# mixer.net
KiCad netlist of a schematic drawn in Altium Designer
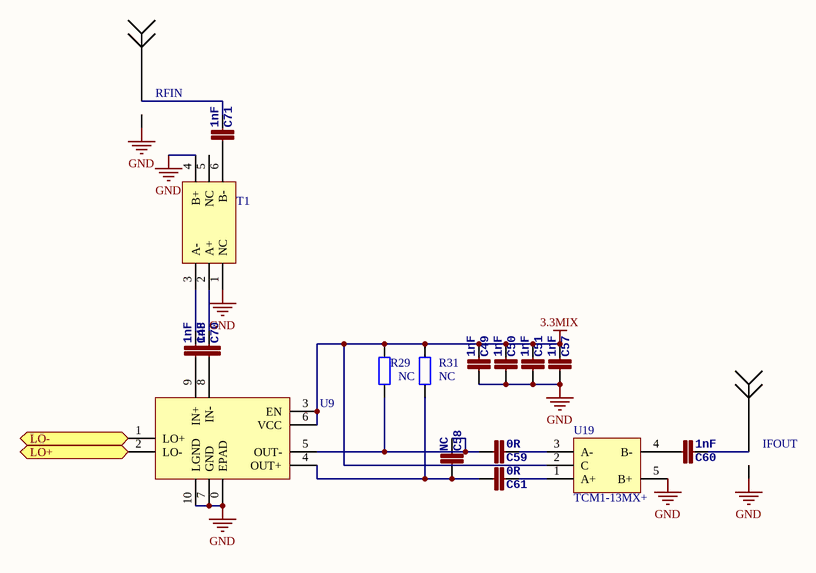
[diagram p0: mixer.SchDoc]

(export (version "E")
  (design (tool "Eeschema 10.0.6"))
  (components
    (comp (ref "C48")
      (value "1nF")
      (footprint "0402")
      (description "<b>Capacitor</b>\nStandard 0603 ceramic capacitor, and 0.1\" leaded capacitor.")
      (fields (field (name "PARTNO") "CC0402ZRY5V7BB104"))
      (libsource (lib "*") (part "CAP0402-CAP"))
    )
    (comp (ref "C49")
      (value "1nF")
      (footprint "0402")
      (description "<b>Capacitor</b>\nStandard 0603 ceramic capacitor, and 0.1\" leaded capacitor.")
      (fields (field (name "PARTNO") "CC0402ZRY5V7BB104"))
      (libsource (lib "*") (part "CAP0402-CAP"))
    )
    (comp (ref "C50")
      (value "1nF")
      (footprint "0402")
      (description "<b>Capacitor</b>\nStandard 0603 ceramic capacitor, and 0.1\" leaded capacitor.")
      (fields (field (name "PARTNO") "CC0402ZRY5V7BB104"))
      (libsource (lib "*") (part "CAP0402-CAP"))
    )
    (comp (ref "C51")
      (value "1nF")
      (footprint "0402")
      (description "<b>Capacitor</b>\nStandard 0603 ceramic capacitor, and 0.1\" leaded capacitor.")
      (fields (field (name "PARTNO") "CC0402ZRY5V7BB104"))
      (libsource (lib "*") (part "CAP0402-CAP"))
    )
    (comp (ref "C57")
      (value "1nF")
      (footprint "0402")
      (description "<b>Capacitor</b>\nStandard 0603 ceramic capacitor, and 0.1\" leaded capacitor.")
      (fields (field (name "PARTNO") "CC0402ZRY5V7BB104"))
      (libsource (lib "*") (part "CAP0402-CAP"))
    )
    (comp (ref "C58")
      (value "NC")
      (footprint "0402")
      (description "<b>Capacitor</b>\nStandard 0603 ceramic capacitor, and 0.1\" leaded capacitor.")
      (fields (field (name "PARTNO") "CC0402ZRY5V7BB104"))
      (libsource (lib "*") (part "CAP0402-CAP"))
    )
    (comp (ref "C59")
      (value "0R")
      (footprint "0402")
      (description "<b>Capacitor</b>\nStandard 0603 ceramic capacitor, and 0.1\" leaded capacitor.")
      (fields (field (name "PARTNO") "CC0402ZRY5V7BB104"))
      (libsource (lib "") (part "CAP0402-CAP_1"))
    )
    (comp (ref "C60")
      (value "1nF")
      (footprint "0402")
      (description "<b>Capacitor</b>\nStandard 0603 ceramic capacitor, and 0.1\" leaded capacitor.")
      (fields (field (name "PARTNO") "CC0402ZRY5V7BB104"))
      (libsource (lib "") (part "CAP0402-CAP_1"))
    )
    (comp (ref "C61")
      (value "0R")
      (footprint "0402")
      (description "<b>Capacitor</b>\nStandard 0603 ceramic capacitor, and 0.1\" leaded capacitor.")
      (fields (field (name "PARTNO") "CC0402ZRY5V7BB104"))
      (libsource (lib "") (part "CAP0402-CAP_1"))
    )
    (comp (ref "C70")
      (value "1nF")
      (footprint "0402")
      (description "<b>Capacitor</b>\nStandard 0603 ceramic capacitor, and 0.1\" leaded capacitor.")
      (fields (field (name "PARTNO") "CC0402ZRY5V7BB104"))
      (libsource (lib "*") (part "CAP0402-CAP"))
    )
    (comp (ref "C71")
      (value "1nF")
      (footprint "0402")
      (description "<b>Capacitor</b>\nStandard 0603 ceramic capacitor, and 0.1\" leaded capacitor.")
      (fields (field (name "PARTNO") "CC0402ZRY5V7BB104"))
      (libsource (lib "*") (part "CAP0402-CAP"))
    )
    (comp (ref "IFOUT") (value "Antenna") (footprint "SMA-2B") (libsource (lib "F4SDR") (part "Antenna")))
    (comp (ref "R29")
      (value "NC")
      (footprint "0402")
      (description "Resistor")
      (fields (field (name "PUBLISHER") "Altium Limited"))
      (libsource (lib "RTC6705") (part "Res2"))
    )
    (comp (ref "R31")
      (value "NC")
      (footprint "0402")
      (description "Resistor")
      (fields (field (name "PUBLISHER") "Altium Limited"))
      (libsource (lib "RTC6705") (part "Res2"))
    )
    (comp (ref "RFIN") (value "Antenna") (footprint "SMA-2B") (libsource (lib "F4SDR") (part "Antenna")))
    (comp (ref "T1")
      (value "TCM1-63AX+")
      (footprint "TCM1-63AX+")
      (libsource (lib "F4SDR") (part "TCM1-63AX+"))
    )
    (comp (ref "U9") (value "LTC5562") (footprint "LTC5562") (libsource (lib "F4SDR") (part "LTC5562")))
    (comp (ref "U19")
      (value "TCM1-13MX+")
      (footprint "TCM-13M+")
      (libsource (lib "F4SDR") (part "TCM1-1-13M+"))
    )
  )
  (nets
    (net (code "1") (name "/LO+") (class "Default")
      (node (ref "U9") (pin "2") (pinfunction "LO-_2") (pintype "passive"))
    )
    (net (code "2") (name "/LO-") (class "Default")
      (node (ref "U9") (pin "1") (pinfunction "LO+_1") (pintype "passive"))
    )
    (net (code "3") (name "3.3MIX") (class "Default")
      (node (ref "C49") (pin "2") (pinfunction "2_2") (pintype "passive"))
      (node (ref "C50") (pin "2") (pinfunction "2_2") (pintype "passive"))
      (node (ref "C51") (pin "2") (pinfunction "2_2") (pintype "passive"))
      (node (ref "C57") (pin "2") (pinfunction "2_2") (pintype "passive"))
      (node (ref "R29") (pin "2") (pinfunction "2_2") (pintype "passive"))
      (node (ref "R31") (pin "2") (pinfunction "2_2") (pintype "passive"))
      (node (ref "U19") (pin "2") (pinfunction "C_2") (pintype "passive"))
      (node (ref "U9") (pin "3") (pinfunction "EN_3") (pintype "passive"))
      (node (ref "U9") (pin "6") (pinfunction "VCC_6") (pintype "passive"))
    )
    (net (code "4") (name "GND") (class "Default")
      (node (ref "C49") (pin "1") (pinfunction "1_1") (pintype "passive"))
      (node (ref "C50") (pin "1") (pinfunction "1_1") (pintype "passive"))
      (node (ref "C51") (pin "1") (pinfunction "1_1") (pintype "passive"))
      (node (ref "C57") (pin "1") (pinfunction "1_1") (pintype "passive"))
      (node (ref "IFOUT") (pin "GND") (pinfunction "G_GND") (pintype "passive"))
      (node (ref "RFIN") (pin "GND") (pinfunction "G_GND") (pintype "passive"))
      (node (ref "T1") (pin "1") (pinfunction "NC_1") (pintype "passive"))
      (node (ref "T1") (pin "4") (pinfunction "B+_4") (pintype "passive"))
      (node (ref "U19") (pin "5") (pinfunction "B+_5") (pintype "passive"))
      (node (ref "U9") (pin "0") (pinfunction "EPAD_0") (pintype "passive"))
      (node (ref "U9") (pin "10") (pinfunction "LGND_10") (pintype "passive"))
      (node (ref "U9") (pin "7") (pinfunction "GND_7") (pintype "passive"))
    )
    (net (code "5") (name "Net-(C60-Pad2)") (class "Default")
      (node (ref "C60") (pin "2") (pinfunction "2_2") (pintype "passive"))
      (node (ref "IFOUT") (pin "1") (pinfunction "1_1") (pintype "passive"))
    )
    (net (code "6") (name "Net-(C71-Pad2)") (class "Default")
      (node (ref "C71") (pin "2") (pinfunction "2_2") (pintype "passive"))
      (node (ref "RFIN") (pin "1") (pinfunction "1_1") (pintype "passive"))
    )
    (net (code "7") (name "Net-(T1-A+)") (class "Default")
      (node (ref "C70") (pin "2") (pinfunction "2_2") (pintype "passive"))
      (node (ref "T1") (pin "2") (pinfunction "A+_2") (pintype "passive"))
    )
    (net (code "8") (name "Net-(T1-A-)") (class "Default")
      (node (ref "C48") (pin "2") (pinfunction "2_2") (pintype "passive"))
      (node (ref "T1") (pin "3") (pinfunction "A-_3") (pintype "passive"))
    )
    (net (code "9") (name "Net-(T1-B-)") (class "Default")
      (node (ref "C71") (pin "1") (pinfunction "1_1") (pintype "passive"))
      (node (ref "T1") (pin "6") (pinfunction "B-_6") (pintype "passive"))
    )
    (net (code "10") (name "Net-(U9-IN+)") (class "Default")
      (node (ref "C48") (pin "1") (pinfunction "1_1") (pintype "passive"))
      (node (ref "U9") (pin "9") (pinfunction "IN+_9") (pintype "passive"))
    )
    (net (code "11") (name "Net-(U9-IN-)") (class "Default")
      (node (ref "C70") (pin "1") (pinfunction "1_1") (pintype "passive"))
      (node (ref "U9") (pin "8") (pinfunction "IN-_8") (pintype "passive"))
    )
    (net (code "12") (name "Net-(U9-OUT+)") (class "Default")
      (node (ref "C58") (pin "1") (pinfunction "1_1") (pintype "passive"))
      (node (ref "C61") (pin "1") (pinfunction "1_1") (pintype "passive"))
      (node (ref "R31") (pin "1") (pinfunction "1_1") (pintype "passive"))
      (node (ref "U9") (pin "4") (pinfunction "OUT+_4") (pintype "passive"))
    )
    (net (code "13") (name "Net-(U9-OUT-)") (class "Default")
      (node (ref "C58") (pin "2") (pinfunction "2_2") (pintype "passive"))
      (node (ref "C59") (pin "1") (pinfunction "1_1") (pintype "passive"))
      (node (ref "R29") (pin "1") (pinfunction "1_1") (pintype "passive"))
      (node (ref "U9") (pin "5") (pinfunction "OUT-_5") (pintype "passive"))
    )
    (net (code "14") (name "Net-(U19-A+)") (class "Default")
      (node (ref "C61") (pin "2") (pinfunction "2_2") (pintype "passive"))
      (node (ref "U19") (pin "1") (pinfunction "A+_1") (pintype "passive"))
    )
    (net (code "15") (name "Net-(U19-A-)") (class "Default")
      (node (ref "C59") (pin "2") (pinfunction "2_2") (pintype "passive"))
      (node (ref "U19") (pin "3") (pinfunction "A-_3") (pintype "passive"))
    )
    (net (code "16") (name "Net-(U19-B-)") (class "Default")
      (node (ref "C60") (pin "1") (pinfunction "1_1") (pintype "passive"))
      (node (ref "U19") (pin "4") (pinfunction "B-_4") (pintype "passive"))
    )
    (net (code "17") (name "unconnected-(T1-NC-Pad5)") (class "Default")
      (node (ref "T1") (pin "5") (pinfunction "NC_5") (pintype "passive"))
    )
  )
)
